# dualHbridge-v6.net
KiCad netlist of a schematic drawn in EAGLE
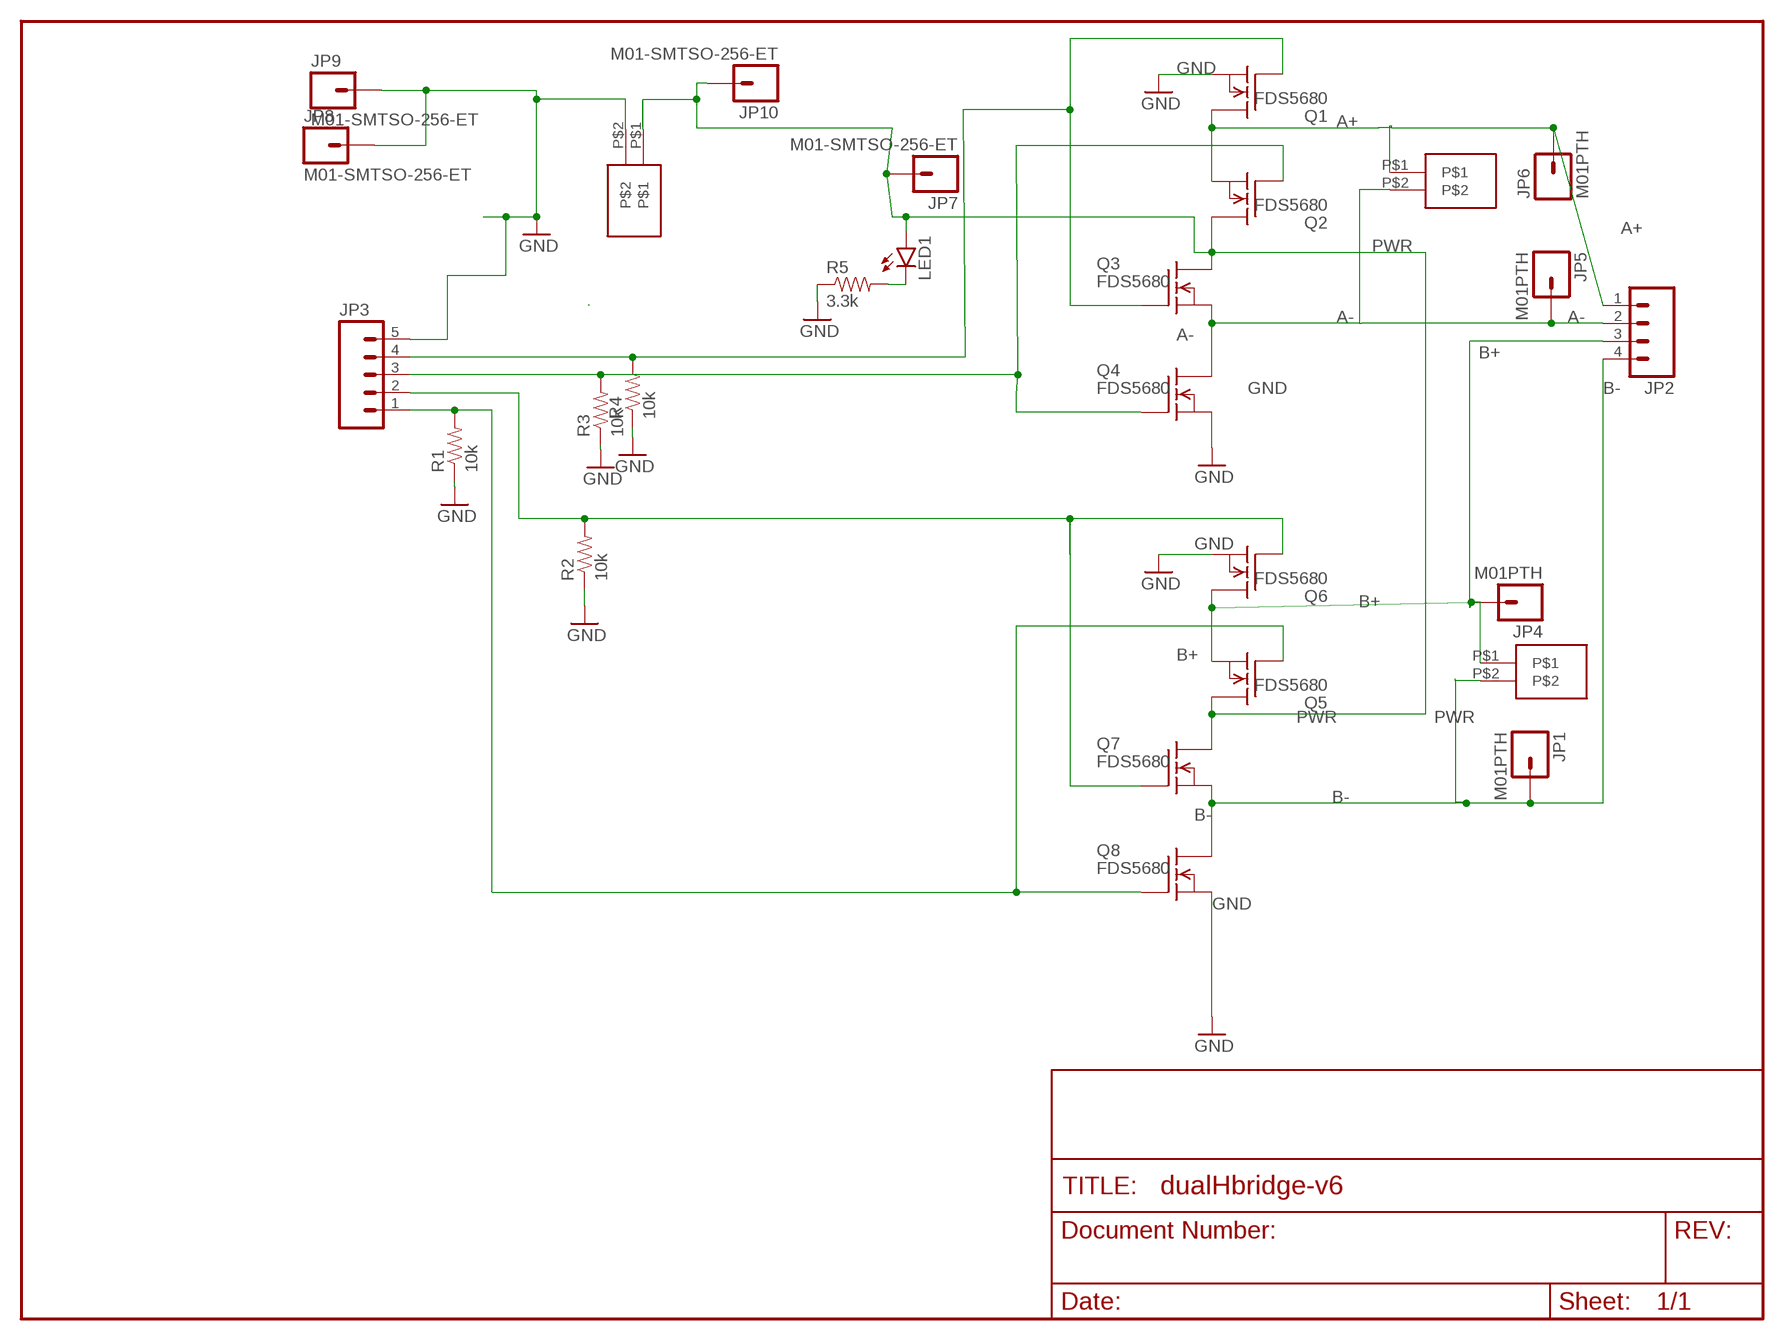
[diagram p0: schematic, sheet 1]

(export (version "E")
  (design (tool "Eeschema 10.0.6"))
  (components
    (comp (ref "JP1")
      (value "M01PTH")
      (footprint "eagle-import:1X01@1")
      (libsource (lib "eagle-import") (part "M01PTH"))
    )
    (comp (ref "JP2")
      (value "M04LONGPADS")
      (footprint "eagle-import:1X04_LONGPADS")
      (libsource (lib "eagle-import") (part "M04LONGPADS"))
    )
    (comp (ref "JP3")
      (value "M05PTH")
      (footprint "eagle-import:1X05")
      (libsource (lib "eagle-import") (part "M05PTH"))
    )
    (comp (ref "JP4")
      (value "M01PTH")
      (footprint "eagle-import:1X01@1")
      (libsource (lib "eagle-import") (part "M01PTH"))
    )
    (comp (ref "JP5")
      (value "M01PTH")
      (footprint "eagle-import:1X01@1")
      (libsource (lib "eagle-import") (part "M01PTH"))
    )
    (comp (ref "JP6")
      (value "M01PTH")
      (footprint "eagle-import:1X01@1")
      (libsource (lib "eagle-import") (part "M01PTH"))
    )
    (comp (ref "JP7")
      (value "M01-SMTSO-256-ET")
      (footprint "eagle-import:SMTSO-256-ET")
      (libsource (lib "eagle-import") (part "M01-SMTSO-256-ET"))
    )
    (comp (ref "JP8")
      (value "M01-SMTSO-256-ET")
      (footprint "eagle-import:SMTSO-256-ET")
      (libsource (lib "eagle-import") (part "M01-SMTSO-256-ET"))
    )
    (comp (ref "JP9")
      (value "M01-SMTSO-256-ET")
      (footprint "eagle-import:SMTSO-256-ET")
      (libsource (lib "eagle-import") (part "M01-SMTSO-256-ET"))
    )
    (comp (ref "JP10")
      (value "M01-SMTSO-256-ET")
      (footprint "eagle-import:SMTSO-256-ET")
      (libsource (lib "eagle-import") (part "M01-SMTSO-256-ET"))
    )
    (comp (ref "LED1")
      (value "LED5MM")
      (footprint "eagle-import:LED5MM")
      (libsource (lib "eagle-import") (part "LED5MM"))
    )
    (comp (ref "Q1")
      (value "FDS5680")
      (footprint "eagle-import:SO-8")
      (libsource (lib "eagle-import") (part "FDS5680"))
    )
    (comp (ref "Q2")
      (value "FDS5680")
      (footprint "eagle-import:SO-8")
      (libsource (lib "eagle-import") (part "FDS5680"))
    )
    (comp (ref "Q3")
      (value "FDS5680")
      (footprint "eagle-import:SO-8")
      (libsource (lib "eagle-import") (part "FDS5680"))
    )
    (comp (ref "Q4")
      (value "FDS5680")
      (footprint "eagle-import:SO-8")
      (libsource (lib "eagle-import") (part "FDS5680"))
    )
    (comp (ref "Q5")
      (value "FDS5680")
      (footprint "eagle-import:SO-8")
      (libsource (lib "eagle-import") (part "FDS5680"))
    )
    (comp (ref "Q6")
      (value "FDS5680")
      (footprint "eagle-import:SO-8")
      (libsource (lib "eagle-import") (part "FDS5680"))
    )
    (comp (ref "Q7")
      (value "FDS5680")
      (footprint "eagle-import:SO-8")
      (libsource (lib "eagle-import") (part "FDS5680"))
    )
    (comp (ref "Q8")
      (value "FDS5680")
      (footprint "eagle-import:SO-8")
      (libsource (lib "eagle-import") (part "FDS5680"))
    )
    (comp (ref "R1")
      (value "10k")
      (footprint "eagle-import:0603-RES")
      (libsource (lib "eagle-import") (part "RESISTOR0603-RES"))
    )
    (comp (ref "R2")
      (value "10k")
      (footprint "eagle-import:0603-RES")
      (libsource (lib "eagle-import") (part "RESISTOR0603-RES"))
    )
    (comp (ref "R3")
      (value "10k")
      (footprint "eagle-import:0603-RES")
      (libsource (lib "eagle-import") (part "RESISTOR0603-RES"))
    )
    (comp (ref "R4")
      (value "10k")
      (footprint "eagle-import:0603-RES")
      (libsource (lib "eagle-import") (part "RESISTOR0603-RES"))
    )
    (comp (ref "R5")
      (value "3.3k")
      (footprint "eagle-import:0603-RES")
      (libsource (lib "eagle-import") (part "RESISTOR0603-RES"))
    )
    (comp (ref "U$1")
      (value "SPRING-TERMINAL")
      (footprint "eagle-import:SPRING-TERMINAL")
      (libsource (lib "eagle-import") (part "SPRING-TERMINAL"))
    )
    (comp (ref "U$2")
      (value "SPRING-TERMINAL")
      (footprint "eagle-import:SPRING-TERMINAL")
      (libsource (lib "eagle-import") (part "SPRING-TERMINAL"))
    )
    (comp (ref "U$3")
      (value "SPRING-TERMINAL")
      (footprint "eagle-import:SPRING-TERMINAL")
      (libsource (lib "eagle-import") (part "SPRING-TERMINAL"))
    )
  )
  (nets
    (net (code "1") (name "/A+") (class "Default")
      (node (ref "JP2") (pin "1") (pinfunction "1_1") (pintype "passive"))
      (node (ref "JP6") (pin "1") (pinfunction "1_1") (pintype "passive"))
      (node (ref "Q1") (pin "5") (pinfunction "D_5") (pintype "passive"))
      (node (ref "Q1") (pin "6") (pinfunction "D_6") (pintype "passive"))
      (node (ref "Q1") (pin "7") (pinfunction "D_7") (pintype "passive"))
      (node (ref "Q1") (pin "8") (pinfunction "D_8") (pintype "passive"))
      (node (ref "Q2") (pin "1") (pinfunction "S_1") (pintype "passive"))
      (node (ref "Q2") (pin "2") (pinfunction "S_2") (pintype "passive"))
      (node (ref "Q2") (pin "3") (pinfunction "S_3") (pintype "passive"))
      (node (ref "U$1") (pin "P$1") (pinfunction "P$1_P$1") (pintype "bidirectional"))
    )
    (net (code "2") (name "/A-") (class "Default")
      (node (ref "JP2") (pin "2") (pinfunction "2_2") (pintype "passive"))
      (node (ref "JP5") (pin "1") (pinfunction "1_1") (pintype "passive"))
      (node (ref "Q3") (pin "1") (pinfunction "S_1") (pintype "passive"))
      (node (ref "Q3") (pin "2") (pinfunction "S_2") (pintype "passive"))
      (node (ref "Q3") (pin "3") (pinfunction "S_3") (pintype "passive"))
      (node (ref "Q4") (pin "5") (pinfunction "D_5") (pintype "passive"))
      (node (ref "Q4") (pin "6") (pinfunction "D_6") (pintype "passive"))
      (node (ref "Q4") (pin "7") (pinfunction "D_7") (pintype "passive"))
      (node (ref "Q4") (pin "8") (pinfunction "D_8") (pintype "passive"))
      (node (ref "U$1") (pin "P$2") (pinfunction "P$2_P$2") (pintype "bidirectional"))
    )
    (net (code "3") (name "/B+") (class "Default")
      (node (ref "JP2") (pin "3") (pinfunction "3_3") (pintype "passive"))
      (node (ref "JP4") (pin "1") (pinfunction "1_1") (pintype "passive"))
      (node (ref "Q5") (pin "1") (pinfunction "S_1") (pintype "passive"))
      (node (ref "Q5") (pin "2") (pinfunction "S_2") (pintype "passive"))
      (node (ref "Q5") (pin "3") (pinfunction "S_3") (pintype "passive"))
      (node (ref "Q6") (pin "5") (pinfunction "D_5") (pintype "passive"))
      (node (ref "Q6") (pin "6") (pinfunction "D_6") (pintype "passive"))
      (node (ref "Q6") (pin "7") (pinfunction "D_7") (pintype "passive"))
      (node (ref "Q6") (pin "8") (pinfunction "D_8") (pintype "passive"))
      (node (ref "U$3") (pin "P$1") (pinfunction "P$1_P$1") (pintype "bidirectional"))
    )
    (net (code "4") (name "/B-") (class "Default")
      (node (ref "JP1") (pin "1") (pinfunction "1_1") (pintype "passive"))
      (node (ref "JP2") (pin "4") (pinfunction "4_4") (pintype "passive"))
      (node (ref "Q7") (pin "1") (pinfunction "S_1") (pintype "passive"))
      (node (ref "Q7") (pin "2") (pinfunction "S_2") (pintype "passive"))
      (node (ref "Q7") (pin "3") (pinfunction "S_3") (pintype "passive"))
      (node (ref "Q8") (pin "5") (pinfunction "D_5") (pintype "passive"))
      (node (ref "Q8") (pin "6") (pinfunction "D_6") (pintype "passive"))
      (node (ref "Q8") (pin "7") (pinfunction "D_7") (pintype "passive"))
      (node (ref "Q8") (pin "8") (pinfunction "D_8") (pintype "passive"))
      (node (ref "U$3") (pin "P$2") (pinfunction "P$2_P$2") (pintype "bidirectional"))
    )
    (net (code "5") (name "/PWR") (class "Default")
      (node (ref "JP10") (pin "P$1") (pinfunction "1_P$1") (pintype "passive"))
      (node (ref "JP7") (pin "P$1") (pinfunction "1_P$1") (pintype "passive"))
      (node (ref "LED1") (pin "A") (pinfunction "A_A") (pintype "passive"))
      (node (ref "Q2") (pin "5") (pinfunction "D_5") (pintype "passive"))
      (node (ref "Q2") (pin "6") (pinfunction "D_6") (pintype "passive"))
      (node (ref "Q2") (pin "7") (pinfunction "D_7") (pintype "passive"))
      (node (ref "Q2") (pin "8") (pinfunction "D_8") (pintype "passive"))
      (node (ref "Q3") (pin "5") (pinfunction "D_5") (pintype "passive"))
      (node (ref "Q3") (pin "6") (pinfunction "D_6") (pintype "passive"))
      (node (ref "Q3") (pin "7") (pinfunction "D_7") (pintype "passive"))
      (node (ref "Q3") (pin "8") (pinfunction "D_8") (pintype "passive"))
      (node (ref "Q5") (pin "5") (pinfunction "D_5") (pintype "passive"))
      (node (ref "Q5") (pin "6") (pinfunction "D_6") (pintype "passive"))
      (node (ref "Q5") (pin "7") (pinfunction "D_7") (pintype "passive"))
      (node (ref "Q5") (pin "8") (pinfunction "D_8") (pintype "passive"))
      (node (ref "Q7") (pin "5") (pinfunction "D_5") (pintype "passive"))
      (node (ref "Q7") (pin "6") (pinfunction "D_6") (pintype "passive"))
      (node (ref "Q7") (pin "7") (pinfunction "D_7") (pintype "passive"))
      (node (ref "Q7") (pin "8") (pinfunction "D_8") (pintype "passive"))
      (node (ref "U$2") (pin "P$1") (pinfunction "P$1_P$1") (pintype "bidirectional"))
    )
    (net (code "6") (name "GND") (class "Default")
      (node (ref "JP3") (pin "5") (pinfunction "5_5") (pintype "passive"))
      (node (ref "JP8") (pin "P$1") (pinfunction "1_P$1") (pintype "passive"))
      (node (ref "JP9") (pin "P$1") (pinfunction "1_P$1") (pintype "passive"))
      (node (ref "Q1") (pin "1") (pinfunction "S_1") (pintype "passive"))
      (node (ref "Q1") (pin "2") (pinfunction "S_2") (pintype "passive"))
      (node (ref "Q1") (pin "3") (pinfunction "S_3") (pintype "passive"))
      (node (ref "Q4") (pin "1") (pinfunction "S_1") (pintype "passive"))
      (node (ref "Q4") (pin "2") (pinfunction "S_2") (pintype "passive"))
      (node (ref "Q4") (pin "3") (pinfunction "S_3") (pintype "passive"))
      (node (ref "Q6") (pin "1") (pinfunction "S_1") (pintype "passive"))
      (node (ref "Q6") (pin "2") (pinfunction "S_2") (pintype "passive"))
      (node (ref "Q6") (pin "3") (pinfunction "S_3") (pintype "passive"))
      (node (ref "Q8") (pin "1") (pinfunction "S_1") (pintype "passive"))
      (node (ref "Q8") (pin "2") (pinfunction "S_2") (pintype "passive"))
      (node (ref "Q8") (pin "3") (pinfunction "S_3") (pintype "passive"))
      (node (ref "R1") (pin "1") (pinfunction "1_1") (pintype "passive"))
      (node (ref "R2") (pin "1") (pinfunction "1_1") (pintype "passive"))
      (node (ref "R3") (pin "1") (pinfunction "1_1") (pintype "passive"))
      (node (ref "R4") (pin "1") (pinfunction "1_1") (pintype "passive"))
      (node (ref "R5") (pin "1") (pinfunction "1_1") (pintype "passive"))
      (node (ref "U$2") (pin "P$2") (pinfunction "P$2_P$2") (pintype "bidirectional"))
    )
    (net (code "7") (name "Net-(LED1-C)") (class "Default")
      (node (ref "LED1") (pin "K") (pinfunction "C_K") (pintype "passive"))
      (node (ref "R5") (pin "2") (pinfunction "2_2") (pintype "passive"))
    )
    (net (code "8") (name "Net-(Q1-G)") (class "Default")
      (node (ref "JP3") (pin "4") (pinfunction "4_4") (pintype "passive"))
      (node (ref "Q1") (pin "4") (pinfunction "G_4") (pintype "passive"))
      (node (ref "Q3") (pin "4") (pinfunction "G_4") (pintype "passive"))
      (node (ref "R4") (pin "2") (pinfunction "2_2") (pintype "passive"))
    )
    (net (code "9") (name "Net-(Q2-G)") (class "Default")
      (node (ref "JP3") (pin "3") (pinfunction "3_3") (pintype "passive"))
      (node (ref "Q2") (pin "4") (pinfunction "G_4") (pintype "passive"))
      (node (ref "Q4") (pin "4") (pinfunction "G_4") (pintype "passive"))
      (node (ref "R3") (pin "2") (pinfunction "2_2") (pintype "passive"))
    )
    (net (code "10") (name "Net-(Q5-G)") (class "Default")
      (node (ref "JP3") (pin "1") (pinfunction "1_1") (pintype "passive"))
      (node (ref "Q5") (pin "4") (pinfunction "G_4") (pintype "passive"))
      (node (ref "Q8") (pin "4") (pinfunction "G_4") (pintype "passive"))
      (node (ref "R1") (pin "2") (pinfunction "2_2") (pintype "passive"))
    )
    (net (code "11") (name "Net-(Q6-G)") (class "Default")
      (node (ref "JP3") (pin "2") (pinfunction "2_2") (pintype "passive"))
      (node (ref "Q6") (pin "4") (pinfunction "G_4") (pintype "passive"))
      (node (ref "Q7") (pin "4") (pinfunction "G_4") (pintype "passive"))
      (node (ref "R2") (pin "2") (pinfunction "2_2") (pintype "passive"))
    )
  )
)
